# diplexer_v4rev0-schematic.net
KiCad netlist of a schematic drawn in EAGLE
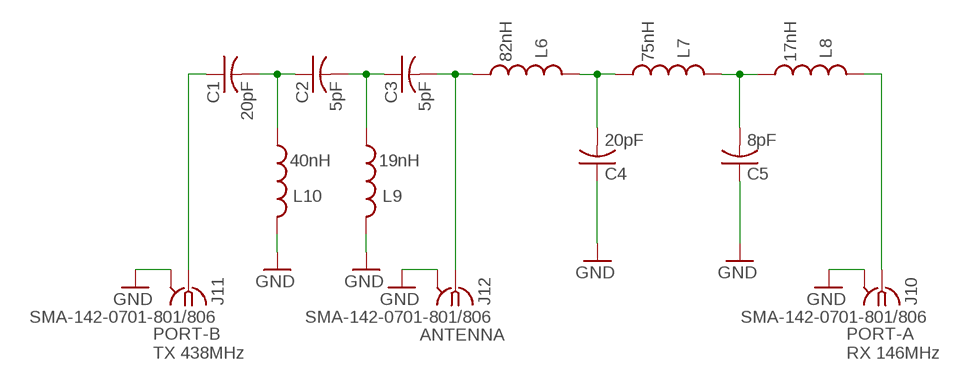
[diagram p0: schematic, sheet 1]

(export (version "E")
  (design (tool "Eeschema 10.0.6"))
  (components
    (comp (ref "C1")
      (value "20pF")
      (footprint "eagle-import:C1608")
      (libsource (lib "eagle-import") (part "C-USC1608"))
    )
    (comp (ref "C2")
      (value "5pF")
      (footprint "eagle-import:C2012")
      (libsource (lib "eagle-import") (part "C-USC2012"))
    )
    (comp (ref "C3")
      (value "5pF")
      (footprint "eagle-import:C2012")
      (libsource (lib "eagle-import") (part "C-USC2012"))
    )
    (comp (ref "C4")
      (value "20pF")
      (footprint "eagle-import:C1608")
      (libsource (lib "eagle-import") (part "C-USC1608"))
    )
    (comp (ref "C5")
      (value "8pF")
      (footprint "eagle-import:C2012")
      (libsource (lib "eagle-import") (part "C-USC2012"))
    )
    (comp (ref "J10")
      (value "SMA-142-0701-801/806")
      (footprint "eagle-import:J502-ND-142-0701-801_806")
      (fields (field (name "MF") "JOHNSON COMPONENTS") (field (name "MPN") "142-0701-801"))
      (libsource (lib "eagle-import") (part "SMA-142-0701-801/806"))
    )
    (comp (ref "J11")
      (value "SMA-142-0701-801/806")
      (footprint "eagle-import:J502-ND-142-0701-801_806")
      (fields (field (name "MF") "JOHNSON COMPONENTS") (field (name "MPN") "142-0701-801"))
      (libsource (lib "eagle-import") (part "SMA-142-0701-801/806"))
    )
    (comp (ref "J12")
      (value "SMA-142-0701-801/806")
      (footprint "eagle-import:J502-ND-142-0701-801_806")
      (fields (field (name "MF") "JOHNSON COMPONENTS") (field (name "MPN") "142-0701-801"))
      (libsource (lib "eagle-import") (part "SMA-142-0701-801/806"))
    )
    (comp (ref "L6")
      (value "82nH")
      (footprint "eagle-import:L01005")
      (libsource (lib "eagle-import") (part "L-US"))
    )
    (comp (ref "L7")
      (value "75nH")
      (footprint "eagle-import:L01005")
      (libsource (lib "eagle-import") (part "L-US"))
    )
    (comp (ref "L8")
      (value "17nH")
      (footprint "eagle-import:L01005")
      (libsource (lib "eagle-import") (part "L-US"))
    )
    (comp (ref "L9")
      (value "19nH")
      (footprint "eagle-import:L01005")
      (libsource (lib "eagle-import") (part "L-US"))
    )
    (comp (ref "L10")
      (value "40nH")
      (footprint "eagle-import:L01005")
      (libsource (lib "eagle-import") (part "L-US"))
    )
  )
  (nets
    (net (code "1") (name "GND") (class "Default")
      (node (ref "C4") (pin "1") (pinfunction "1_1") (pintype "passive"))
      (node (ref "C5") (pin "1") (pinfunction "1_1") (pintype "passive"))
      (node (ref "J10") (pin "G@1") (pinfunction "GND_G@1") (pintype "power_in"))
      (node (ref "J11") (pin "G@1") (pinfunction "GND_G@1") (pintype "power_in"))
      (node (ref "J12") (pin "G@1") (pinfunction "GND_G@1") (pintype "power_in"))
      (node (ref "L10") (pin "2") (pinfunction "2_2") (pintype "passive"))
      (node (ref "L9") (pin "2") (pinfunction "2_2") (pintype "passive"))
    )
    (net (code "2") (name "Net-(C1-Pad1)") (class "Default")
      (node (ref "C1") (pin "1") (pinfunction "1_1") (pintype "passive"))
      (node (ref "J11") (pin "1") (pinfunction "1_1") (pintype "passive"))
    )
    (net (code "3") (name "Net-(C1-Pad2)") (class "Default")
      (node (ref "C1") (pin "2") (pinfunction "2_2") (pintype "passive"))
      (node (ref "C2") (pin "1") (pinfunction "1_1") (pintype "passive"))
      (node (ref "L10") (pin "1") (pinfunction "1_1") (pintype "passive"))
    )
    (net (code "4") (name "Net-(C2-Pad2)") (class "Default")
      (node (ref "C2") (pin "2") (pinfunction "2_2") (pintype "passive"))
      (node (ref "C3") (pin "1") (pinfunction "1_1") (pintype "passive"))
      (node (ref "L9") (pin "1") (pinfunction "1_1") (pintype "passive"))
    )
    (net (code "5") (name "Net-(C3-Pad2)") (class "Default")
      (node (ref "C3") (pin "2") (pinfunction "2_2") (pintype "passive"))
      (node (ref "J12") (pin "1") (pinfunction "1_1") (pintype "passive"))
      (node (ref "L6") (pin "1") (pinfunction "1_1") (pintype "passive"))
    )
    (net (code "6") (name "Net-(C4-Pad2)") (class "Default")
      (node (ref "C4") (pin "2") (pinfunction "2_2") (pintype "passive"))
      (node (ref "L6") (pin "2") (pinfunction "2_2") (pintype "passive"))
      (node (ref "L7") (pin "1") (pinfunction "1_1") (pintype "passive"))
    )
    (net (code "7") (name "Net-(C5-Pad2)") (class "Default")
      (node (ref "C5") (pin "2") (pinfunction "2_2") (pintype "passive"))
      (node (ref "L7") (pin "2") (pinfunction "2_2") (pintype "passive"))
      (node (ref "L8") (pin "1") (pinfunction "1_1") (pintype "passive"))
    )
    (net (code "8") (name "Net-(J10-Pad1)") (class "Default")
      (node (ref "J10") (pin "1") (pinfunction "1_1") (pintype "passive"))
      (node (ref "L8") (pin "2") (pinfunction "2_2") (pintype "passive"))
    )
  )
)
